# Relay_Controller_V1_0.net
KiCad netlist of a schematic drawn in EAGLE
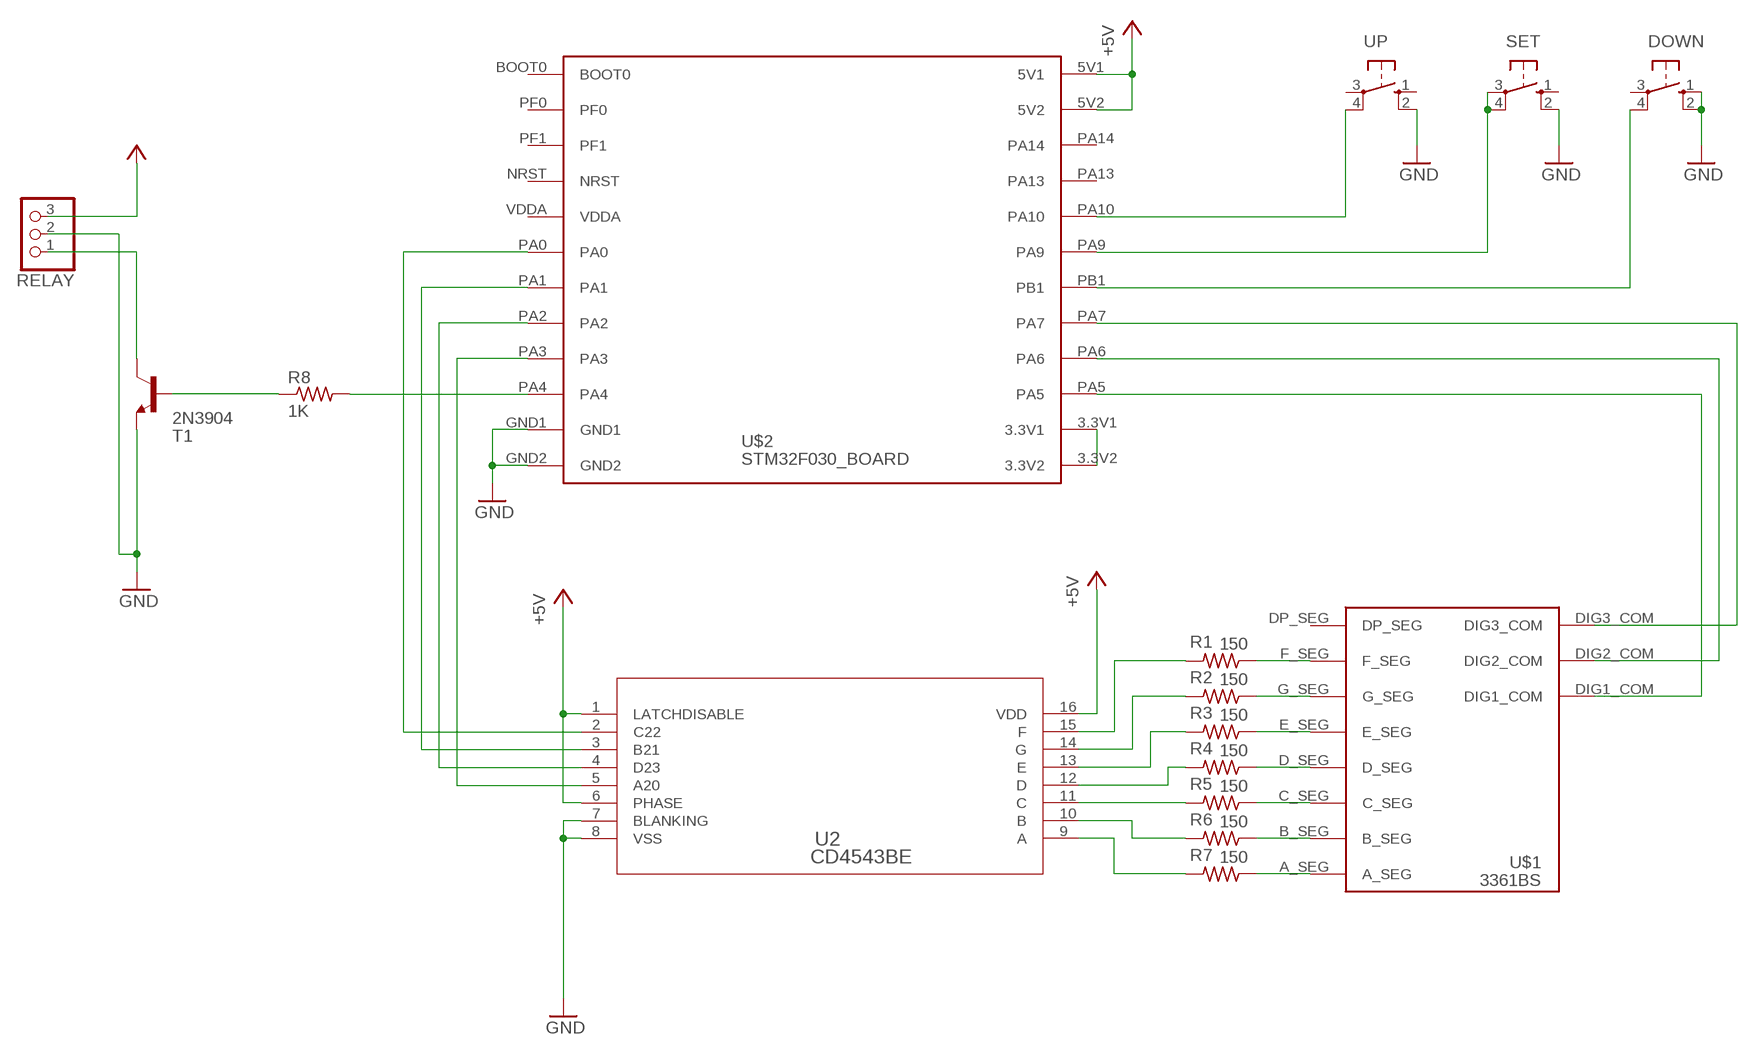
[diagram p0: schematic, sheet 1]

(export (version "E")
  (design (tool "Eeschema 10.0.6"))
  (components
    (comp (ref "DOWN")
      (value "10-XX")
      (footprint "eagle-import:B3F-10XX")
      (fields (field (name "MPN") "B3F-1000"))
      (libsource (lib "eagle-import") (part "10-XX"))
    )
    (comp (ref "R1")
      (value "150")
      (footprint "eagle-import:0207_7")
      (libsource (lib "eagle-import") (part "R-US_0207/7"))
    )
    (comp (ref "R2")
      (value "150")
      (footprint "eagle-import:0207_7")
      (libsource (lib "eagle-import") (part "R-US_0207/7"))
    )
    (comp (ref "R3")
      (value "150")
      (footprint "eagle-import:0207_7")
      (libsource (lib "eagle-import") (part "R-US_0207/7"))
    )
    (comp (ref "R4")
      (value "150")
      (footprint "eagle-import:0207_7")
      (libsource (lib "eagle-import") (part "R-US_0207/7"))
    )
    (comp (ref "R5")
      (value "150")
      (footprint "eagle-import:0207_7")
      (libsource (lib "eagle-import") (part "R-US_0207/7"))
    )
    (comp (ref "R6")
      (value "150")
      (footprint "eagle-import:0207_7")
      (libsource (lib "eagle-import") (part "R-US_0207/7"))
    )
    (comp (ref "R7")
      (value "150")
      (footprint "eagle-import:0207_7")
      (libsource (lib "eagle-import") (part "R-US_0207/7"))
    )
    (comp (ref "R8")
      (value "1K")
      (footprint "eagle-import:0207_7")
      (libsource (lib "eagle-import") (part "R-US_0207/7"))
    )
    (comp (ref "RELAY")
      (value "PINHD-1X3")
      (footprint "eagle-import:1X03")
      (libsource (lib "eagle-import") (part "PINHD-1X3"))
    )
    (comp (ref "SET")
      (value "10-XX")
      (footprint "eagle-import:B3F-10XX")
      (fields (field (name "MPN") "B3F-1000"))
      (libsource (lib "eagle-import") (part "10-XX"))
    )
    (comp (ref "T1")
      (value "2N3904")
      (footprint "eagle-import:TO92")
      (libsource (lib "eagle-import") (part "2N3904"))
    )
    (comp (ref "U$1")
      (value "3361BS")
      (footprint "eagle-import:3361BS")
      (libsource (lib "eagle-import") (part "3361BS"))
    )
    (comp (ref "U$2")
      (value "STM32F030_BOARD")
      (footprint "eagle-import:STM32F030F4P6_BOARD")
      (libsource (lib "eagle-import") (part "STM32F030_BOARD"))
    )
    (comp (ref "U2")
      (value "CD4543BE")
      (footprint "eagle-import:N16")
      (fields
        (field (name "GENERIC_PART_NUMBER") "CD4543B")
        (field (name "MANUFACTURER") "Texas Instruments")
      )
      (libsource (lib "eagle-import") (part "CD4543BE"))
    )
    (comp (ref "UP")
      (value "10-XX")
      (footprint "eagle-import:B3F-10XX")
      (fields (field (name "MPN") "B3F-1000"))
      (libsource (lib "eagle-import") (part "10-XX"))
    )
  )
  (nets
    (net (code "1") (name "+5V") (class "Default")
      (node (ref "RELAY") (pin "3") (pinfunction "3_3") (pintype "passive"))
      (node (ref "U$2") (pin "5V1") (pinfunction "5V1_5V1") (pintype "bidirectional"))
      (node (ref "U$2") (pin "5V2") (pinfunction "5V2_5V2") (pintype "bidirectional"))
      (node (ref "U2") (pin "1") (pinfunction "LATCHDISABLE_1") (pintype "passive"))
      (node (ref "U2") (pin "16") (pinfunction "VDD_16") (pintype "power_in"))
      (node (ref "U2") (pin "6") (pinfunction "PHASE_6") (pintype "passive"))
    )
    (net (code "2") (name "GND") (class "Default")
      (node (ref "DOWN") (pin "1") (pinfunction "S_1") (pintype "passive"))
      (node (ref "DOWN") (pin "2") (pinfunction "S1_2") (pintype "passive"))
      (node (ref "RELAY") (pin "2") (pinfunction "2_2") (pintype "passive"))
      (node (ref "SET") (pin "2") (pinfunction "S1_2") (pintype "passive"))
      (node (ref "T1") (pin "3") (pinfunction "E_3") (pintype "passive"))
      (node (ref "U$2") (pin "GND1") (pinfunction "GND1_GND1") (pintype "bidirectional"))
      (node (ref "U$2") (pin "GND2") (pinfunction "GND2_GND2") (pintype "bidirectional"))
      (node (ref "U2") (pin "7") (pinfunction "BLANKING_7") (pintype "passive"))
      (node (ref "U2") (pin "8") (pinfunction "VSS_8") (pintype "power_in"))
      (node (ref "UP") (pin "2") (pinfunction "S1_2") (pintype "passive"))
    )
    (net (code "3") (name "Net-(DOWN-P1)") (class "Default")
      (node (ref "DOWN") (pin "4") (pinfunction "P1_4") (pintype "passive"))
      (node (ref "U$2") (pin "PB1") (pinfunction "PB1_PB1") (pintype "bidirectional"))
    )
    (net (code "4") (name "Net-(R1-Pad1)") (class "Default")
      (node (ref "R1") (pin "1") (pinfunction "1_1") (pintype "passive"))
      (node (ref "U$1") (pin "F_SEG") (pinfunction "F_SEG_F_SEG") (pintype "bidirectional"))
    )
    (net (code "5") (name "Net-(R2-Pad1)") (class "Default")
      (node (ref "R2") (pin "1") (pinfunction "1_1") (pintype "passive"))
      (node (ref "U$1") (pin "G_SEG") (pinfunction "G_SEG_G_SEG") (pintype "bidirectional"))
    )
    (net (code "6") (name "Net-(R3-Pad1)") (class "Default")
      (node (ref "R3") (pin "1") (pinfunction "1_1") (pintype "passive"))
      (node (ref "U$1") (pin "E_SEG") (pinfunction "E_SEG_E_SEG") (pintype "bidirectional"))
    )
    (net (code "7") (name "Net-(R4-Pad1)") (class "Default")
      (node (ref "R4") (pin "1") (pinfunction "1_1") (pintype "passive"))
      (node (ref "U$1") (pin "D_SEG") (pinfunction "D_SEG_D_SEG") (pintype "bidirectional"))
    )
    (net (code "8") (name "Net-(R5-Pad1)") (class "Default")
      (node (ref "R5") (pin "1") (pinfunction "1_1") (pintype "passive"))
      (node (ref "U$1") (pin "C_SEG") (pinfunction "C_SEG_C_SEG") (pintype "bidirectional"))
    )
    (net (code "9") (name "Net-(R6-Pad1)") (class "Default")
      (node (ref "R6") (pin "1") (pinfunction "1_1") (pintype "passive"))
      (node (ref "U$1") (pin "B_SEG") (pinfunction "B_SEG_B_SEG") (pintype "bidirectional"))
    )
    (net (code "10") (name "Net-(R7-Pad1)") (class "Default")
      (node (ref "R7") (pin "1") (pinfunction "1_1") (pintype "passive"))
      (node (ref "U$1") (pin "A_SEG") (pinfunction "A_SEG_A_SEG") (pintype "bidirectional"))
    )
    (net (code "11") (name "Net-(R8-Pad2)") (class "Default")
      (node (ref "R8") (pin "2") (pinfunction "2_2") (pintype "passive"))
      (node (ref "U$2") (pin "PA4") (pinfunction "PA4_PA4") (pintype "bidirectional"))
    )
    (net (code "12") (name "Net-(SET-P)") (class "Default")
      (node (ref "SET") (pin "3") (pinfunction "P_3") (pintype "passive"))
      (node (ref "SET") (pin "4") (pinfunction "P1_4") (pintype "passive"))
      (node (ref "U$2") (pin "PA9") (pinfunction "PA9_PA9") (pintype "bidirectional"))
    )
    (net (code "13") (name "Net-(T1-B)") (class "Default")
      (node (ref "R8") (pin "1") (pinfunction "1_1") (pintype "passive"))
      (node (ref "T1") (pin "2") (pinfunction "B_2") (pintype "passive"))
    )
    (net (code "14") (name "Net-(T1-C)") (class "Default")
      (node (ref "RELAY") (pin "1") (pinfunction "1_1") (pintype "passive"))
      (node (ref "T1") (pin "1") (pinfunction "C_1") (pintype "passive"))
    )
    (net (code "15") (name "Net-(U$1-PadDIG1_COM)") (class "Default")
      (node (ref "U$1") (pin "DIG1_COM") (pinfunction "DIG1_COM_DIG1_COM") (pintype "bidirectional"))
      (node (ref "U$2") (pin "PA5") (pinfunction "PA5_PA5") (pintype "bidirectional"))
    )
    (net (code "16") (name "Net-(U$1-PadDIG2_COM)") (class "Default")
      (node (ref "U$1") (pin "DIG2_COM") (pinfunction "DIG2_COM_DIG2_COM") (pintype "bidirectional"))
      (node (ref "U$2") (pin "PA6") (pinfunction "PA6_PA6") (pintype "bidirectional"))
    )
    (net (code "17") (name "Net-(U$1-PadDIG3_COM)") (class "Default")
      (node (ref "U$1") (pin "DIG3_COM") (pinfunction "DIG3_COM_DIG3_COM") (pintype "bidirectional"))
      (node (ref "U$2") (pin "PA7") (pinfunction "PA7_PA7") (pintype "bidirectional"))
    )
    (net (code "18") (name "Net-(U$2-Pad3.3V1)") (class "Default")
      (node (ref "U$2") (pin "3.3V1") (pinfunction "3.3V1_3.3V1") (pintype "bidirectional"))
      (node (ref "U$2") (pin "3.3V2") (pinfunction "3.3V2_3.3V2") (pintype "bidirectional"))
    )
    (net (code "19") (name "Net-(U2-A)") (class "Default")
      (node (ref "R7") (pin "2") (pinfunction "2_2") (pintype "passive"))
      (node (ref "U2") (pin "9") (pinfunction "A_9") (pintype "passive"))
    )
    (net (code "20") (name "Net-(U2-A20)") (class "Default")
      (node (ref "U$2") (pin "PA3") (pinfunction "PA3_PA3") (pintype "bidirectional"))
      (node (ref "U2") (pin "5") (pinfunction "A20_5") (pintype "passive"))
    )
    (net (code "21") (name "Net-(U2-B)") (class "Default")
      (node (ref "R6") (pin "2") (pinfunction "2_2") (pintype "passive"))
      (node (ref "U2") (pin "10") (pinfunction "B_10") (pintype "passive"))
    )
    (net (code "22") (name "Net-(U2-B21)") (class "Default")
      (node (ref "U$2") (pin "PA1") (pinfunction "PA1_PA1") (pintype "bidirectional"))
      (node (ref "U2") (pin "3") (pinfunction "B21_3") (pintype "passive"))
    )
    (net (code "23") (name "Net-(U2-C)") (class "Default")
      (node (ref "R5") (pin "2") (pinfunction "2_2") (pintype "passive"))
      (node (ref "U2") (pin "11") (pinfunction "C_11") (pintype "passive"))
    )
    (net (code "24") (name "Net-(U2-C22)") (class "Default")
      (node (ref "U$2") (pin "PA0") (pinfunction "PA0_PA0") (pintype "bidirectional"))
      (node (ref "U2") (pin "2") (pinfunction "C22_2") (pintype "passive"))
    )
    (net (code "25") (name "Net-(U2-D)") (class "Default")
      (node (ref "R4") (pin "2") (pinfunction "2_2") (pintype "passive"))
      (node (ref "U2") (pin "12") (pinfunction "D_12") (pintype "passive"))
    )
    (net (code "26") (name "Net-(U2-D23)") (class "Default")
      (node (ref "U$2") (pin "PA2") (pinfunction "PA2_PA2") (pintype "bidirectional"))
      (node (ref "U2") (pin "4") (pinfunction "D23_4") (pintype "passive"))
    )
    (net (code "27") (name "Net-(U2-E)") (class "Default")
      (node (ref "R3") (pin "2") (pinfunction "2_2") (pintype "passive"))
      (node (ref "U2") (pin "13") (pinfunction "E_13") (pintype "passive"))
    )
    (net (code "28") (name "Net-(U2-F)") (class "Default")
      (node (ref "R1") (pin "2") (pinfunction "2_2") (pintype "passive"))
      (node (ref "U2") (pin "15") (pinfunction "F_15") (pintype "passive"))
    )
    (net (code "29") (name "Net-(U2-G)") (class "Default")
      (node (ref "R2") (pin "2") (pinfunction "2_2") (pintype "passive"))
      (node (ref "U2") (pin "14") (pinfunction "G_14") (pintype "passive"))
    )
    (net (code "30") (name "Net-(UP-P1)") (class "Default")
      (node (ref "U$2") (pin "PA10") (pinfunction "PA10_PA10") (pintype "bidirectional"))
      (node (ref "UP") (pin "4") (pinfunction "P1_4") (pintype "passive"))
    )
    (net (code "31") (name "unconnected-(DOWN-P-Pad3)") (class "Default")
      (node (ref "DOWN") (pin "3") (pinfunction "P_3") (pintype "passive"))
    )
    (net (code "32") (name "unconnected-(SET-S-Pad1)") (class "Default")
      (node (ref "SET") (pin "1") (pinfunction "S_1") (pintype "passive"))
    )
    (net (code "33") (name "unconnected-(U$1-PadDP_SEG)") (class "Default")
      (node (ref "U$1") (pin "DP_SEG") (pinfunction "DP_SEG_DP_SEG") (pintype "bidirectional"))
    )
    (net (code "34") (name "unconnected-(U$2-PadBOOT0)") (class "Default")
      (node (ref "U$2") (pin "BOOT0") (pinfunction "BOOT0_BOOT0") (pintype "bidirectional"))
    )
    (net (code "35") (name "unconnected-(U$2-PadNRST)") (class "Default")
      (node (ref "U$2") (pin "NRST") (pinfunction "NRST_NRST") (pintype "bidirectional"))
    )
    (net (code "36") (name "unconnected-(U$2-PadPA13)") (class "Default")
      (node (ref "U$2") (pin "PA13") (pinfunction "PA13_PA13") (pintype "bidirectional"))
    )
    (net (code "37") (name "unconnected-(U$2-PadPA14)") (class "Default")
      (node (ref "U$2") (pin "PA14") (pinfunction "PA14_PA14") (pintype "bidirectional"))
    )
    (net (code "38") (name "unconnected-(U$2-PadPF0)") (class "Default")
      (node (ref "U$2") (pin "PF0") (pinfunction "PF0_PF0") (pintype "bidirectional"))
    )
    (net (code "39") (name "unconnected-(U$2-PadPF1)") (class "Default")
      (node (ref "U$2") (pin "PF1") (pinfunction "PF1_PF1") (pintype "bidirectional"))
    )
    (net (code "40") (name "unconnected-(U$2-PadVDDA)") (class "Default")
      (node (ref "U$2") (pin "VDDA") (pinfunction "VDDA_VDDA") (pintype "bidirectional"))
    )
    (net (code "41") (name "unconnected-(UP-P-Pad3)") (class "Default")
      (node (ref "UP") (pin "3") (pinfunction "P_3") (pintype "passive"))
    )
    (net (code "42") (name "unconnected-(UP-S-Pad1)") (class "Default")
      (node (ref "UP") (pin "1") (pinfunction "S_1") (pintype "passive"))
    )
  )
)
